# MegaSound9x_HaGeHa_SIP_v1.net
KiCad netlist of a schematic drawn in EAGLE
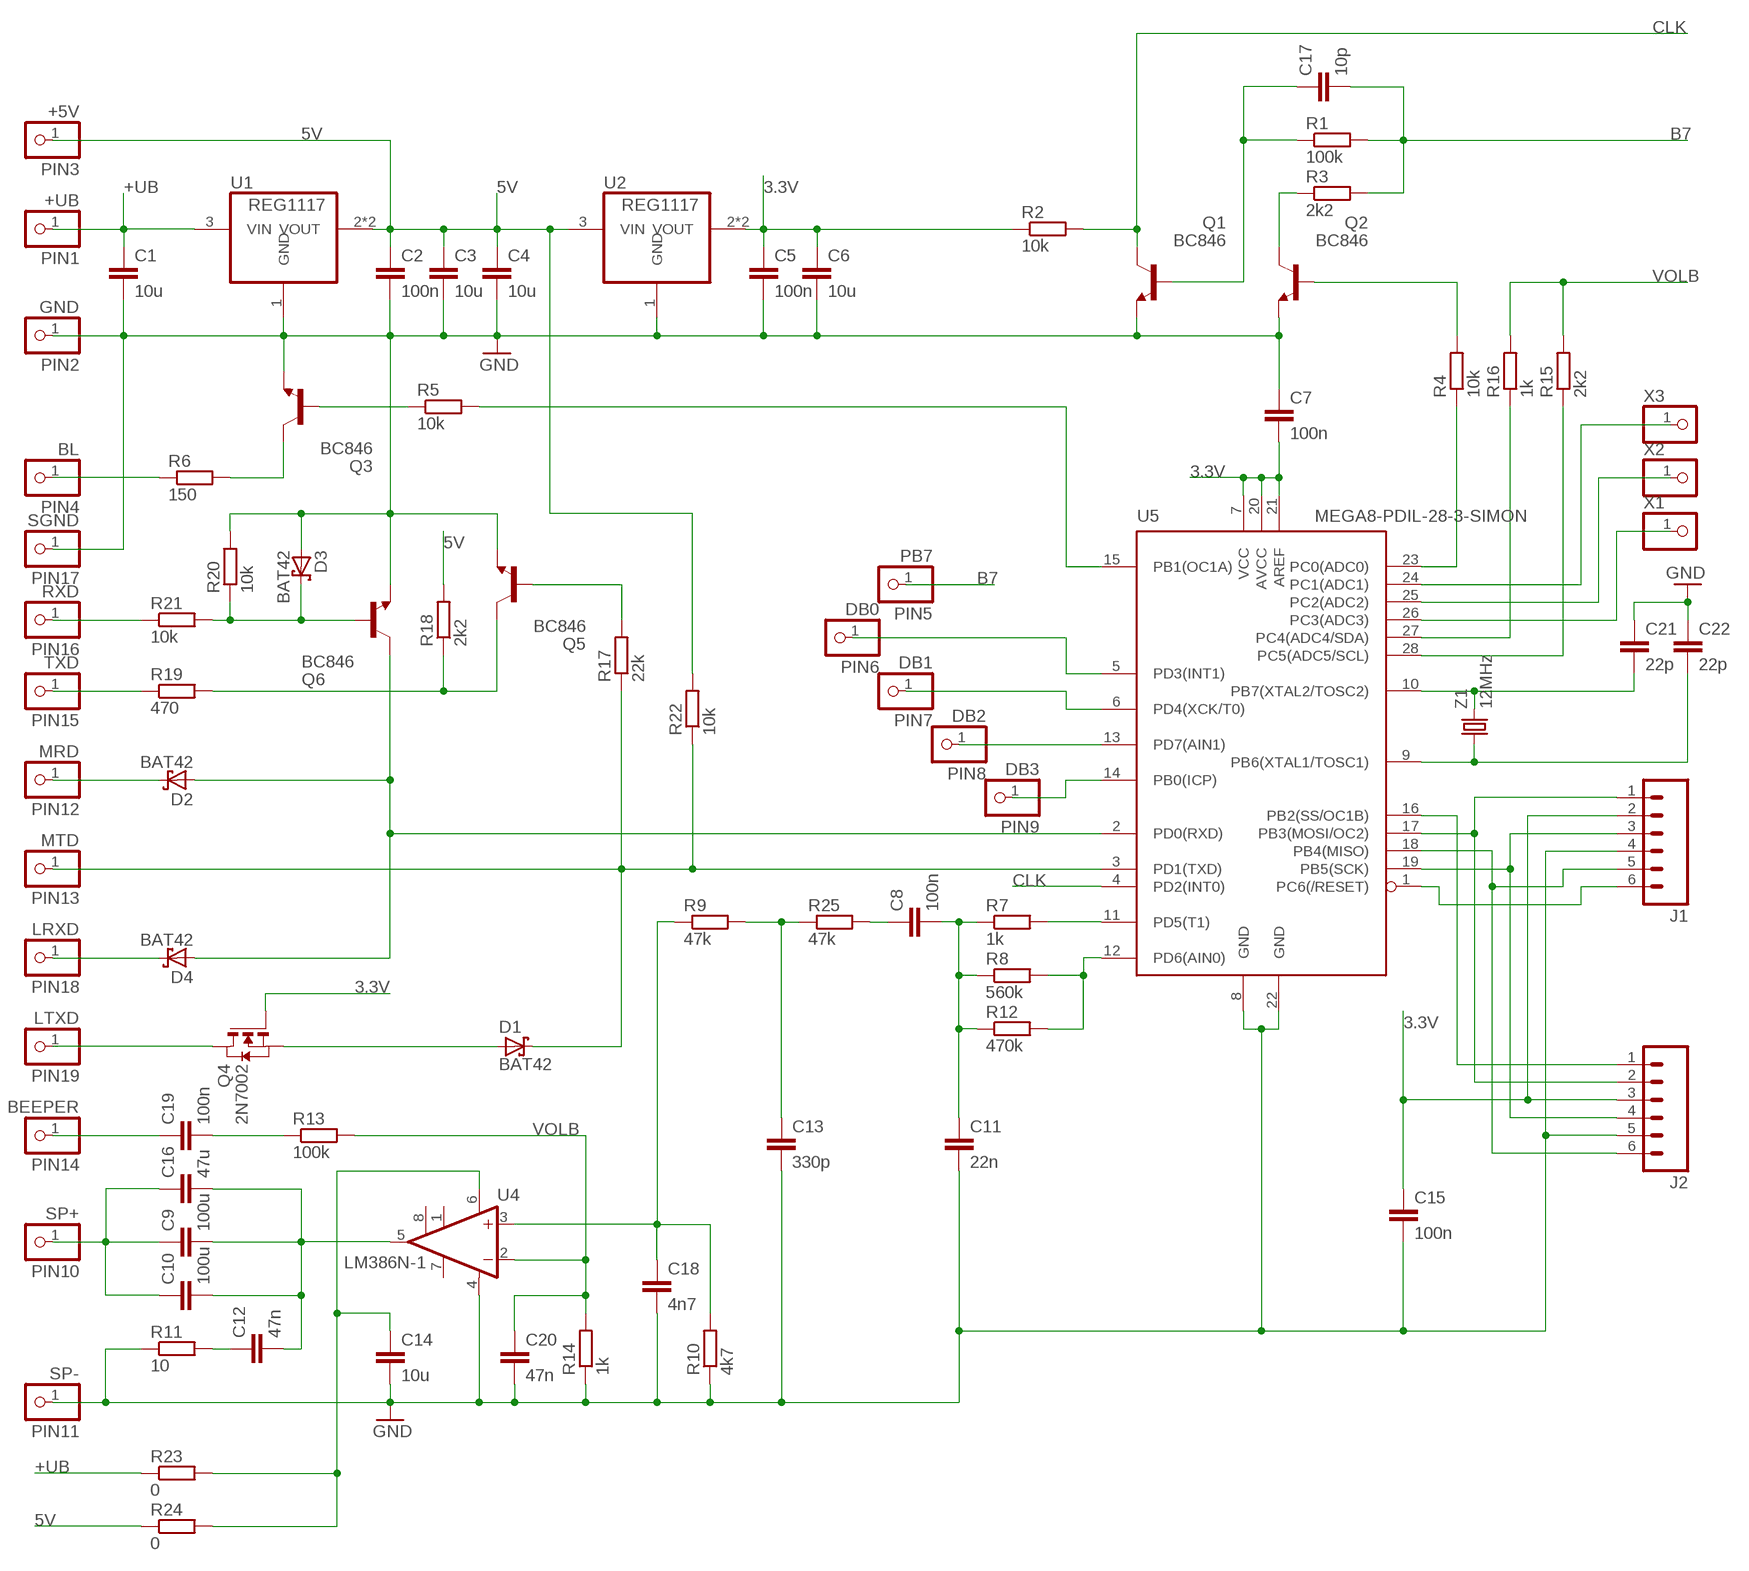
[diagram p0: schematic, sheet 1]

(export (version "E")
  (design (tool "Eeschema 10.0.6"))
  (components
    (comp (ref "+5V")
      (value "PIN3")
      (footprint "eagle-import:1X01")
      (libsource (lib "eagle-import") (part "PINHD-1X1"))
    )
    (comp (ref "+UB")
      (value "PIN1")
      (footprint "eagle-import:1X01")
      (libsource (lib "eagle-import") (part "PINHD-1X1"))
    )
    (comp (ref "BEEPER")
      (value "PIN14")
      (footprint "eagle-import:1X01")
      (libsource (lib "eagle-import") (part "PINHD-1X1"))
    )
    (comp (ref "BL")
      (value "PIN4")
      (footprint "eagle-import:1X01")
      (libsource (lib "eagle-import") (part "PINHD-1X1"))
    )
    (comp (ref "C1")
      (value "10u")
      (footprint "eagle-import:C1206")
      (libsource (lib "eagle-import") (part "C-EUC1206"))
    )
    (comp (ref "C2")
      (value "100n")
      (footprint "eagle-import:C1206")
      (libsource (lib "eagle-import") (part "C-EUC1206"))
    )
    (comp (ref "C3")
      (value "10u")
      (footprint "eagle-import:C1206")
      (libsource (lib "eagle-import") (part "C-EUC1206"))
    )
    (comp (ref "C4")
      (value "10u")
      (footprint "eagle-import:C1206")
      (libsource (lib "eagle-import") (part "C-EUC1206"))
    )
    (comp (ref "C5")
      (value "100n")
      (footprint "eagle-import:C1206")
      (libsource (lib "eagle-import") (part "C-EUC1206"))
    )
    (comp (ref "C6")
      (value "10u")
      (footprint "eagle-import:C1206")
      (libsource (lib "eagle-import") (part "C-EUC1206"))
    )
    (comp (ref "C7")
      (value "100n")
      (footprint "eagle-import:C1206")
      (libsource (lib "eagle-import") (part "C-EUC1206"))
    )
    (comp (ref "C8")
      (value "100n")
      (footprint "eagle-import:C1206")
      (libsource (lib "eagle-import") (part "C-EUC1206"))
    )
    (comp (ref "C9")
      (value "100u")
      (footprint "eagle-import:C1206")
      (libsource (lib "eagle-import") (part "C-EUC1206"))
    )
    (comp (ref "C10")
      (value "100u")
      (footprint "eagle-import:C1206")
      (libsource (lib "eagle-import") (part "C-EUC1206"))
    )
    (comp (ref "C11")
      (value "22n")
      (footprint "eagle-import:C1206")
      (libsource (lib "eagle-import") (part "C-EUC1206"))
    )
    (comp (ref "C12")
      (value "47n")
      (footprint "eagle-import:C1206")
      (libsource (lib "eagle-import") (part "C-EUC1206"))
    )
    (comp (ref "C13")
      (value "330p")
      (footprint "eagle-import:C1206")
      (libsource (lib "eagle-import") (part "C-EUC1206"))
    )
    (comp (ref "C14")
      (value "10u")
      (footprint "eagle-import:C1206")
      (libsource (lib "eagle-import") (part "C-EUC1206"))
    )
    (comp (ref "C15")
      (value "100n")
      (footprint "eagle-import:C1206")
      (libsource (lib "eagle-import") (part "C-EUC1206"))
    )
    (comp (ref "C16")
      (value "47u")
      (footprint "eagle-import:C1206")
      (libsource (lib "eagle-import") (part "C-EUC1206"))
    )
    (comp (ref "C17")
      (value "10p")
      (footprint "eagle-import:C1206")
      (libsource (lib "eagle-import") (part "C-EUC1206"))
    )
    (comp (ref "C18")
      (value "4n7")
      (footprint "eagle-import:C1206")
      (libsource (lib "eagle-import") (part "C-EUC1206"))
    )
    (comp (ref "C19")
      (value "100n")
      (footprint "eagle-import:C1206")
      (libsource (lib "eagle-import") (part "C-EUC1206"))
    )
    (comp (ref "C20")
      (value "47n")
      (footprint "eagle-import:C1206")
      (libsource (lib "eagle-import") (part "C-EUC1206"))
    )
    (comp (ref "C21")
      (value "22p")
      (footprint "eagle-import:C1206")
      (libsource (lib "eagle-import") (part "C-EUC1206"))
    )
    (comp (ref "C22")
      (value "22p")
      (footprint "eagle-import:C1206")
      (libsource (lib "eagle-import") (part "C-EUC1206"))
    )
    (comp (ref "D1")
      (value "BAT42")
      (footprint "eagle-import:SOD123")
      (libsource (lib "eagle-import") (part "BAT42"))
    )
    (comp (ref "D2")
      (value "BAT42")
      (footprint "eagle-import:SOD123")
      (libsource (lib "eagle-import") (part "BAT42"))
    )
    (comp (ref "D3")
      (value "BAT42")
      (footprint "eagle-import:SOD123")
      (libsource (lib "eagle-import") (part "BAT42"))
    )
    (comp (ref "D4")
      (value "BAT42")
      (footprint "eagle-import:SOD123")
      (libsource (lib "eagle-import") (part "BAT42"))
    )
    (comp (ref "DB0")
      (value "PIN6")
      (footprint "eagle-import:1X01")
      (libsource (lib "eagle-import") (part "PINHD-1X1"))
    )
    (comp (ref "DB1")
      (value "PIN7")
      (footprint "eagle-import:1X01")
      (libsource (lib "eagle-import") (part "PINHD-1X1"))
    )
    (comp (ref "DB2")
      (value "PIN8")
      (footprint "eagle-import:1X01")
      (libsource (lib "eagle-import") (part "PINHD-1X1"))
    )
    (comp (ref "DB3")
      (value "PIN9")
      (footprint "eagle-import:1X01")
      (libsource (lib "eagle-import") (part "PINHD-1X1"))
    )
    (comp (ref "GND")
      (value "PIN2")
      (footprint "eagle-import:1X01")
      (libsource (lib "eagle-import") (part "PINHD-1X1"))
    )
    (comp (ref "J1")
      (value "M06SIP")
      (footprint "eagle-import:1X06")
      (libsource (lib "eagle-import") (part "M06SIP"))
    )
    (comp (ref "J2")
      (value "M06SIP")
      (footprint "eagle-import:1X06")
      (libsource (lib "eagle-import") (part "M06SIP"))
    )
    (comp (ref "LRXD")
      (value "PIN18")
      (footprint "eagle-import:1X01")
      (libsource (lib "eagle-import") (part "PINHD-1X1"))
    )
    (comp (ref "LTXD")
      (value "PIN19")
      (footprint "eagle-import:1X01")
      (libsource (lib "eagle-import") (part "PINHD-1X1"))
    )
    (comp (ref "MRD")
      (value "PIN12")
      (footprint "eagle-import:1X01")
      (libsource (lib "eagle-import") (part "PINHD-1X1"))
    )
    (comp (ref "MTD")
      (value "PIN13")
      (footprint "eagle-import:1X01")
      (libsource (lib "eagle-import") (part "PINHD-1X1"))
    )
    (comp (ref "PB7")
      (value "PIN5")
      (footprint "eagle-import:1X01")
      (libsource (lib "eagle-import") (part "PINHD-1X1"))
    )
    (comp (ref "Q1")
      (value "BC846")
      (footprint "eagle-import:SOT23")
      (libsource (lib "eagle-import") (part "BC846"))
    )
    (comp (ref "Q2")
      (value "BC846")
      (footprint "eagle-import:SOT23")
      (libsource (lib "eagle-import") (part "BC846"))
    )
    (comp (ref "Q3")
      (value "BC846")
      (footprint "eagle-import:SOT23")
      (libsource (lib "eagle-import") (part "BC846"))
    )
    (comp (ref "Q4")
      (value "2N7002")
      (footprint "eagle-import:SOT-23")
      (libsource (lib "eagle-import") (part "NMOSSOT23"))
    )
    (comp (ref "Q5")
      (value "BC846")
      (footprint "eagle-import:SOT23")
      (libsource (lib "eagle-import") (part "BC846"))
    )
    (comp (ref "Q6")
      (value "BC846")
      (footprint "eagle-import:SOT23")
      (libsource (lib "eagle-import") (part "BC846"))
    )
    (comp (ref "R1")
      (value "100k")
      (footprint "eagle-import:R1206")
      (libsource (lib "eagle-import") (part "R-EU_R1206"))
    )
    (comp (ref "R2")
      (value "10k")
      (footprint "eagle-import:R1206")
      (libsource (lib "eagle-import") (part "R-EU_R1206"))
    )
    (comp (ref "R3")
      (value "2k2")
      (footprint "eagle-import:R1206")
      (libsource (lib "eagle-import") (part "R-EU_R1206"))
    )
    (comp (ref "R4")
      (value "10k")
      (footprint "eagle-import:R1206")
      (libsource (lib "eagle-import") (part "R-EU_R1206"))
    )
    (comp (ref "R5")
      (value "10k")
      (footprint "eagle-import:R1206")
      (libsource (lib "eagle-import") (part "R-EU_R1206"))
    )
    (comp (ref "R6")
      (value "150")
      (footprint "eagle-import:R1206")
      (libsource (lib "eagle-import") (part "R-EU_R1206"))
    )
    (comp (ref "R7")
      (value "1k")
      (footprint "eagle-import:R1206")
      (libsource (lib "eagle-import") (part "R-EU_R1206"))
    )
    (comp (ref "R8")
      (value "560k")
      (footprint "eagle-import:R1206")
      (libsource (lib "eagle-import") (part "R-EU_R1206"))
    )
    (comp (ref "R9")
      (value "47k")
      (footprint "eagle-import:R1206")
      (libsource (lib "eagle-import") (part "R-EU_R1206"))
    )
    (comp (ref "R10")
      (value "4k7")
      (footprint "eagle-import:R1206")
      (libsource (lib "eagle-import") (part "R-EU_R1206"))
    )
    (comp (ref "R11")
      (value "10")
      (footprint "eagle-import:R1206")
      (libsource (lib "eagle-import") (part "R-EU_R1206"))
    )
    (comp (ref "R12")
      (value "470k")
      (footprint "eagle-import:R1206")
      (libsource (lib "eagle-import") (part "R-EU_R1206"))
    )
    (comp (ref "R13")
      (value "100k")
      (footprint "eagle-import:R1206")
      (libsource (lib "eagle-import") (part "R-EU_R1206"))
    )
    (comp (ref "R14")
      (value "1k")
      (footprint "eagle-import:R1206")
      (libsource (lib "eagle-import") (part "R-EU_R1206"))
    )
    (comp (ref "R15")
      (value "2k2")
      (footprint "eagle-import:R1206")
      (libsource (lib "eagle-import") (part "R-EU_R1206"))
    )
    (comp (ref "R16")
      (value "1k")
      (footprint "eagle-import:R1206")
      (libsource (lib "eagle-import") (part "R-EU_R1206"))
    )
    (comp (ref "R17")
      (value "22k")
      (footprint "eagle-import:R1206")
      (libsource (lib "eagle-import") (part "R-EU_R1206"))
    )
    (comp (ref "R18")
      (value "2k2")
      (footprint "eagle-import:R1206")
      (libsource (lib "eagle-import") (part "R-EU_R1206"))
    )
    (comp (ref "R19")
      (value "470")
      (footprint "eagle-import:R1206")
      (libsource (lib "eagle-import") (part "R-EU_R1206"))
    )
    (comp (ref "R20")
      (value "10k")
      (footprint "eagle-import:R1206")
      (libsource (lib "eagle-import") (part "R-EU_R1206"))
    )
    (comp (ref "R21")
      (value "10k")
      (footprint "eagle-import:R1206")
      (libsource (lib "eagle-import") (part "R-EU_R1206"))
    )
    (comp (ref "R22")
      (value "10k")
      (footprint "eagle-import:R1206")
      (libsource (lib "eagle-import") (part "R-EU_R1206"))
    )
    (comp (ref "R23")
      (value "0")
      (footprint "eagle-import:R1206")
      (libsource (lib "eagle-import") (part "R-EU_R1206"))
    )
    (comp (ref "R24")
      (value "0")
      (footprint "eagle-import:R1206")
      (libsource (lib "eagle-import") (part "R-EU_R1206"))
    )
    (comp (ref "R25")
      (value "47k")
      (footprint "eagle-import:R1206")
      (libsource (lib "eagle-import") (part "R-EU_R1206"))
    )
    (comp (ref "RXD")
      (value "PIN16")
      (footprint "eagle-import:1X01")
      (libsource (lib "eagle-import") (part "PINHD-1X1"))
    )
    (comp (ref "SGND")
      (value "PIN17")
      (footprint "eagle-import:1X01")
      (libsource (lib "eagle-import") (part "PINHD-1X1"))
    )
    (comp (ref "SP+")
      (value "PIN10")
      (footprint "eagle-import:1X01")
      (libsource (lib "eagle-import") (part "PINHD-1X1"))
    )
    (comp (ref "SP-")
      (value "PIN11")
      (footprint "eagle-import:1X01")
      (libsource (lib "eagle-import") (part "PINHD-1X1"))
    )
    (comp (ref "TXD")
      (value "PIN15")
      (footprint "eagle-import:1X01")
      (libsource (lib "eagle-import") (part "PINHD-1X1"))
    )
    (comp (ref "U1")
      (value "REG1117")
      (footprint "eagle-import:SOT223")
      (libsource (lib "eagle-import") (part "REG1117"))
    )
    (comp (ref "U2")
      (value "REG1117")
      (footprint "eagle-import:SOT223")
      (fields
        (field (name "MPN") "REG1117")
        (field (name "OC_FARNELL") "1097566")
        (field (name "OC_NEWARK") "14P6981")
      )
      (libsource (lib "eagle-import") (part "REG1117"))
    )
    (comp (ref "U4")
      (value "LM386N-1")
      (footprint "eagle-import:DIL08")
      (libsource (lib "eagle-import") (part "LM386?-N1"))
    )
    (comp (ref "U5")
      (value "MEGA8-PDIL-28-3-SIMON")
      (footprint "eagle-import:DIL28-3-SIMON")
      (libsource (lib "eagle-import") (part "MEGA8-PDIL-28-3-SIMON"))
    )
    (comp (ref "X1")
      (value "PINHD-1X1")
      (footprint "eagle-import:1X01")
      (libsource (lib "eagle-import") (part "PINHD-1X1"))
    )
    (comp (ref "X2")
      (value "PINHD-1X1")
      (footprint "eagle-import:1X01")
      (libsource (lib "eagle-import") (part "PINHD-1X1"))
    )
    (comp (ref "X3")
      (value "PINHD-1X1")
      (footprint "eagle-import:1X01")
      (libsource (lib "eagle-import") (part "PINHD-1X1"))
    )
    (comp (ref "Z1")
      (value "12MHz")
      (footprint "eagle-import:HC49US")
      (libsource (lib "eagle-import") (part "CRYSTALHC49US"))
    )
  )
  (nets
    (net (code "1") (name "/+UB") (class "Default")
      (node (ref "+UB") (pin "1") (pinfunction "1_1") (pintype "passive"))
      (node (ref "C1") (pin "1") (pinfunction "1_1") (pintype "passive"))
      (node (ref "R23") (pin "1") (pinfunction "1_1") (pintype "passive"))
      (node (ref "U1") (pin "3") (pinfunction "VIN_3") (pintype "input"))
    )
    (net (code "2") (name "/3.3V") (class "Default")
      (node (ref "C15") (pin "1") (pinfunction "1_1") (pintype "passive"))
      (node (ref "C5") (pin "1") (pinfunction "1_1") (pintype "passive"))
      (node (ref "C6") (pin "1") (pinfunction "1_1") (pintype "passive"))
      (node (ref "C7") (pin "2") (pinfunction "2_2") (pintype "passive"))
      (node (ref "J1") (pin "2") (pinfunction "2_2") (pintype "passive"))
      (node (ref "J2") (pin "3") (pinfunction "3_3") (pintype "passive"))
      (node (ref "Q4") (pin "3") (pinfunction "G_3") (pintype "passive"))
      (node (ref "R2") (pin "1") (pinfunction "1_1") (pintype "passive"))
      (node (ref "U2") (pin "2") (pinfunction "VOUT_2") (pintype "output"))
      (node (ref "U2") (pin "4") (pinfunction "VOUT_4") (pintype "output"))
      (node (ref "U5") (pin "20") (pinfunction "AVCC_20") (pintype "power_in"))
      (node (ref "U5") (pin "21") (pinfunction "AREF_21") (pintype "passive"))
      (node (ref "U5") (pin "7") (pinfunction "VCC_7") (pintype "power_in"))
    )
    (net (code "3") (name "/5V") (class "Default")
      (node (ref "+5V") (pin "1") (pinfunction "1_1") (pintype "passive"))
      (node (ref "C2") (pin "1") (pinfunction "1_1") (pintype "passive"))
      (node (ref "C3") (pin "1") (pinfunction "1_1") (pintype "passive"))
      (node (ref "C4") (pin "1") (pinfunction "1_1") (pintype "passive"))
      (node (ref "R18") (pin "2") (pinfunction "2_2") (pintype "passive"))
      (node (ref "R22") (pin "2") (pinfunction "2_2") (pintype "passive"))
      (node (ref "R24") (pin "1") (pinfunction "1_1") (pintype "passive"))
      (node (ref "U1") (pin "2") (pinfunction "VOUT_2") (pintype "output"))
      (node (ref "U1") (pin "4") (pinfunction "VOUT_4") (pintype "output"))
      (node (ref "U2") (pin "3") (pinfunction "VIN_3") (pintype "input"))
    )
    (net (code "4") (name "/B7") (class "Default")
      (node (ref "C17") (pin "2") (pinfunction "2_2") (pintype "passive"))
      (node (ref "PB7") (pin "1") (pinfunction "1_1") (pintype "passive"))
      (node (ref "R1") (pin "2") (pinfunction "2_2") (pintype "passive"))
      (node (ref "R3") (pin "2") (pinfunction "2_2") (pintype "passive"))
    )
    (net (code "5") (name "/CLK") (class "Default")
      (node (ref "Q1") (pin "3") (pinfunction "C_3") (pintype "passive"))
      (node (ref "R2") (pin "2") (pinfunction "2_2") (pintype "passive"))
      (node (ref "U5") (pin "4") (pinfunction "PD2(INT0)_4") (pintype "bidirectional"))
    )
    (net (code "6") (name "/VOLB") (class "Default")
      (node (ref "C20") (pin "1") (pinfunction "1_1") (pintype "passive"))
      (node (ref "R13") (pin "2") (pinfunction "2_2") (pintype "passive"))
      (node (ref "R14") (pin "2") (pinfunction "2_2") (pintype "passive"))
      (node (ref "R15") (pin "2") (pinfunction "2_2") (pintype "passive"))
      (node (ref "R16") (pin "2") (pinfunction "2_2") (pintype "passive"))
      (node (ref "U4") (pin "2") (pinfunction "-IN_2") (pintype "input"))
    )
    (net (code "7") (name "GND") (class "Default")
      (node (ref "C1") (pin "2") (pinfunction "2_2") (pintype "passive"))
      (node (ref "C11") (pin "2") (pinfunction "2_2") (pintype "passive"))
      (node (ref "C13") (pin "2") (pinfunction "2_2") (pintype "passive"))
      (node (ref "C14") (pin "2") (pinfunction "2_2") (pintype "passive"))
      (node (ref "C15") (pin "2") (pinfunction "2_2") (pintype "passive"))
      (node (ref "C18") (pin "2") (pinfunction "2_2") (pintype "passive"))
      (node (ref "C2") (pin "2") (pinfunction "2_2") (pintype "passive"))
      (node (ref "C20") (pin "2") (pinfunction "2_2") (pintype "passive"))
      (node (ref "C21") (pin "1") (pinfunction "1_1") (pintype "passive"))
      (node (ref "C22") (pin "1") (pinfunction "1_1") (pintype "passive"))
      (node (ref "C3") (pin "2") (pinfunction "2_2") (pintype "passive"))
      (node (ref "C4") (pin "2") (pinfunction "2_2") (pintype "passive"))
      (node (ref "C5") (pin "2") (pinfunction "2_2") (pintype "passive"))
      (node (ref "C6") (pin "2") (pinfunction "2_2") (pintype "passive"))
      (node (ref "C7") (pin "1") (pinfunction "1_1") (pintype "passive"))
      (node (ref "D3") (pin "A") (pinfunction "A_A") (pintype "passive"))
      (node (ref "GND") (pin "1") (pinfunction "1_1") (pintype "passive"))
      (node (ref "J1") (pin "4") (pinfunction "4_4") (pintype "passive"))
      (node (ref "J2") (pin "5") (pinfunction "5_5") (pintype "passive"))
      (node (ref "Q1") (pin "2") (pinfunction "E_2") (pintype "passive"))
      (node (ref "Q2") (pin "2") (pinfunction "E_2") (pintype "passive"))
      (node (ref "Q3") (pin "2") (pinfunction "E_2") (pintype "passive"))
      (node (ref "Q5") (pin "2") (pinfunction "E_2") (pintype "passive"))
      (node (ref "Q6") (pin "2") (pinfunction "E_2") (pintype "passive"))
      (node (ref "R10") (pin "1") (pinfunction "1_1") (pintype "passive"))
      (node (ref "R11") (pin "1") (pinfunction "1_1") (pintype "passive"))
      (node (ref "R14") (pin "1") (pinfunction "1_1") (pintype "passive"))
      (node (ref "R20") (pin "2") (pinfunction "2_2") (pintype "passive"))
      (node (ref "SGND") (pin "1") (pinfunction "1_1") (pintype "passive"))
      (node (ref "SP-") (pin "1") (pinfunction "1_1") (pintype "passive"))
      (node (ref "U1") (pin "1") (pinfunction "GND_1") (pintype "power_in"))
      (node (ref "U2") (pin "1") (pinfunction "GND_1") (pintype "power_in"))
      (node (ref "U4") (pin "4") (pinfunction "GND_4") (pintype "power_in"))
      (node (ref "U5") (pin "22") (pinfunction "GND_22") (pintype "power_in"))
      (node (ref "U5") (pin "8") (pinfunction "GND_8") (pintype "power_in"))
    )
    (net (code "8") (name "Net-(BEEPER-Pad1)") (class "Default")
      (node (ref "BEEPER") (pin "1") (pinfunction "1_1") (pintype "passive"))
      (node (ref "C19") (pin "1") (pinfunction "1_1") (pintype "passive"))
    )
    (net (code "9") (name "Net-(BL-Pad1)") (class "Default")
      (node (ref "BL") (pin "1") (pinfunction "1_1") (pintype "passive"))
      (node (ref "R6") (pin "1") (pinfunction "1_1") (pintype "passive"))
    )
    (net (code "10") (name "Net-(C8-Pad1)") (class "Default")
      (node (ref "C8") (pin "1") (pinfunction "1_1") (pintype "passive"))
      (node (ref "R25") (pin "2") (pinfunction "2_2") (pintype "passive"))
    )
    (net (code "11") (name "Net-(C10-Pad1)") (class "Default")
      (node (ref "C10") (pin "1") (pinfunction "1_1") (pintype "passive"))
      (node (ref "C16") (pin "1") (pinfunction "1_1") (pintype "passive"))
      (node (ref "C9") (pin "1") (pinfunction "1_1") (pintype "passive"))
      (node (ref "SP+") (pin "1") (pinfunction "1_1") (pintype "passive"))
    )
    (net (code "12") (name "Net-(C11-Pad1)") (class "Default")
      (node (ref "C11") (pin "1") (pinfunction "1_1") (pintype "passive"))
      (node (ref "C8") (pin "2") (pinfunction "2_2") (pintype "passive"))
      (node (ref "R12") (pin "1") (pinfunction "1_1") (pintype "passive"))
      (node (ref "R7") (pin "1") (pinfunction "1_1") (pintype "passive"))
      (node (ref "R8") (pin "1") (pinfunction "1_1") (pintype "passive"))
    )
    (net (code "13") (name "Net-(C12-Pad1)") (class "Default")
      (node (ref "C12") (pin "1") (pinfunction "1_1") (pintype "passive"))
      (node (ref "R11") (pin "2") (pinfunction "2_2") (pintype "passive"))
    )
    (net (code "14") (name "Net-(C13-Pad1)") (class "Default")
      (node (ref "C13") (pin "1") (pinfunction "1_1") (pintype "passive"))
      (node (ref "R25") (pin "1") (pinfunction "1_1") (pintype "passive"))
      (node (ref "R9") (pin "2") (pinfunction "2_2") (pintype "passive"))
    )
    (net (code "15") (name "Net-(C19-Pad2)") (class "Default")
      (node (ref "C19") (pin "2") (pinfunction "2_2") (pintype "passive"))
      (node (ref "R13") (pin "1") (pinfunction "1_1") (pintype "passive"))
    )
    (net (code "16") (name "Net-(D2-PadC)") (class "Default")
      (node (ref "D2") (pin "C") (pinfunction "C_C") (pintype "passive"))
      (node (ref "MRD") (pin "1") (pinfunction "1_1") (pintype "passive"))
    )
    (net (code "17") (name "Net-(D4-PadC)") (class "Default")
      (node (ref "D4") (pin "C") (pinfunction "C_C") (pintype "passive"))
      (node (ref "LRXD") (pin "1") (pinfunction "1_1") (pintype "passive"))
    )
    (net (code "18") (name "Net-(Q1-B)") (class "Default")
      (node (ref "C17") (pin "1") (pinfunction "1_1") (pintype "passive"))
      (node (ref "Q1") (pin "1") (pinfunction "B_1") (pintype "passive"))
      (node (ref "R1") (pin "1") (pinfunction "1_1") (pintype "passive"))
    )
    (net (code "19") (name "Net-(Q2-B)") (class "Default")
      (node (ref "Q2") (pin "1") (pinfunction "B_1") (pintype "passive"))
      (node (ref "R4") (pin "2") (pinfunction "2_2") (pintype "passive"))
    )
    (net (code "20") (name "Net-(Q2-C)") (class "Default")
      (node (ref "Q2") (pin "3") (pinfunction "C_3") (pintype "passive"))
      (node (ref "R3") (pin "1") (pinfunction "1_1") (pintype "passive"))
    )
    (net (code "21") (name "Net-(Q3-B)") (class "Default")
      (node (ref "Q3") (pin "1") (pinfunction "B_1") (pintype "passive"))
      (node (ref "R5") (pin "1") (pinfunction "1_1") (pintype "passive"))
    )
    (net (code "22") (name "Net-(Q3-C)") (class "Default")
      (node (ref "Q3") (pin "3") (pinfunction "C_3") (pintype "passive"))
      (node (ref "R6") (pin "2") (pinfunction "2_2") (pintype "passive"))
    )
    (net (code "23") (name "Net-(Q4-D)") (class "Default")
      (node (ref "LTXD") (pin "1") (pinfunction "1_1") (pintype "passive"))
      (node (ref "Q4") (pin "1") (pinfunction "D_1") (pintype "passive"))
    )
    (net (code "24") (name "Net-(Q4-S)") (class "Default")
      (node (ref "D1") (pin "A") (pinfunction "A_A") (pintype "passive"))
      (node (ref "Q4") (pin "2") (pinfunction "S_2") (pintype "passive"))
    )
    (net (code "25") (name "Net-(Q5-B)") (class "Default")
      (node (ref "Q5") (pin "1") (pinfunction "B_1") (pintype "passive"))
      (node (ref "R17") (pin "2") (pinfunction "2_2") (pintype "passive"))
    )
    (net (code "26") (name "Net-(Q5-C)") (class "Default")
      (node (ref "Q5") (pin "3") (pinfunction "C_3") (pintype "passive"))
      (node (ref "R18") (pin "1") (pinfunction "1_1") (pintype "passive"))
      (node (ref "R19") (pin "2") (pinfunction "2_2") (pintype "passive"))
    )
    (net (code "27") (name "Net-(Q6-B)") (class "Default")
      (node (ref "D3") (pin "C") (pinfunction "C_C") (pintype "passive"))
      (node (ref "Q6") (pin "1") (pinfunction "B_1") (pintype "passive"))
      (node (ref "R20") (pin "1") (pinfunction "1_1") (pintype "passive"))
      (node (ref "R21") (pin "2") (pinfunction "2_2") (pintype "passive"))
    )
    (net (code "28") (name "Net-(Q6-C)") (class "Default")
      (node (ref "D2") (pin "A") (pinfunction "A_A") (pintype "passive"))
      (node (ref "D4") (pin "A") (pinfunction "A_A") (pintype "passive"))
      (node (ref "Q6") (pin "3") (pinfunction "C_3") (pintype "passive"))
      (node (ref "U5") (pin "2") (pinfunction "PD0(RXD)_2") (pintype "bidirectional"))
    )
    (net (code "29") (name "Net-(R19-Pad1)") (class "Default")
      (node (ref "R19") (pin "1") (pinfunction "1_1") (pintype "passive"))
      (node (ref "TXD") (pin "1") (pinfunction "1_1") (pintype "passive"))
    )
    (net (code "30") (name "Net-(R21-Pad1)") (class "Default")
      (node (ref "R21") (pin "1") (pinfunction "1_1") (pintype "passive"))
      (node (ref "RXD") (pin "1") (pinfunction "1_1") (pintype "passive"))
    )
    (net (code "31") (name "Net-(U4-+IN)") (class "Default")
      (node (ref "C18") (pin "1") (pinfunction "1_1") (pintype "passive"))
      (node (ref "R10") (pin "2") (pinfunction "2_2") (pintype "passive"))
      (node (ref "R9") (pin "1") (pinfunction "1_1") (pintype "passive"))
      (node (ref "U4") (pin "3") (pinfunction "+IN_3") (pintype "input"))
    )
    (net (code "32") (name "Net-(U4-OUT)") (class "Default")
      (node (ref "C10") (pin "2") (pinfunction "2_2") (pintype "passive"))
      (node (ref "C12") (pin "2") (pinfunction "2_2") (pintype "passive"))
      (node (ref "C16") (pin "2") (pinfunction "2_2") (pintype "passive"))
      (node (ref "C9") (pin "2") (pinfunction "2_2") (pintype "passive"))
      (node (ref "U4") (pin "5") (pinfunction "OUT_5") (pintype "output"))
    )
    (net (code "33") (name "Net-(U4-VS)") (class "Default")
      (node (ref "C14") (pin "1") (pinfunction "1_1") (pintype "passive"))
      (node (ref "R23") (pin "2") (pinfunction "2_2") (pintype "passive"))
      (node (ref "R24") (pin "2") (pinfunction "2_2") (pintype "passive"))
      (node (ref "U4") (pin "6") (pinfunction "VS_6") (pintype "power_in"))
    )
    (net (code "34") (name "Net-(U5-PB0(ICP))") (class "Default")
      (node (ref "DB3") (pin "1") (pinfunction "1_1") (pintype "passive"))
      (node (ref "U5") (pin "14") (pinfunction "PB0(ICP)_14") (pintype "bidirectional"))
    )
    (net (code "35") (name "Net-(U5-PB1(OC1A))") (class "Default")
      (node (ref "R5") (pin "2") (pinfunction "2_2") (pintype "passive"))
      (node (ref "U5") (pin "15") (pinfunction "PB1(OC1A)_15") (pintype "bidirectional"))
    )
    (net (code "36") (name "Net-(U5-PB2(SS{slash}OC1B))") (class "Default")
      (node (ref "J2") (pin "1") (pinfunction "1_1") (pintype "passive"))
      (node (ref "U5") (pin "16") (pinfunction "PB2(SS/OC1B)_16") (pintype "bidirectional"))
    )
    (net (code "37") (name "Net-(U5-PB3(MOSI{slash}OC2))") (class "Default")
      (node (ref "J1") (pin "1") (pinfunction "1_1") (pintype "passive"))
      (node (ref "J2") (pin "2") (pinfunction "2_2") (pintype "passive"))
      (node (ref "U5") (pin "17") (pinfunction "PB3(MOSI/OC2)_17") (pintype "bidirectional"))
    )
    (net (code "38") (name "Net-(U5-PB4(MISO))") (class "Default")
      (node (ref "J1") (pin "5") (pinfunction "5_5") (pintype "passive"))
      (node (ref "J2") (pin "6") (pinfunction "6_6") (pintype "passive"))
      (node (ref "U5") (pin "18") (pinfunction "PB4(MISO)_18") (pintype "bidirectional"))
    )
    (net (code "39") (name "Net-(U5-PB5(SCK))") (class "Default")
      (node (ref "J1") (pin "3") (pinfunction "3_3") (pintype "passive"))
      (node (ref "J2") (pin "4") (pinfunction "4_4") (pintype "passive"))
      (node (ref "U5") (pin "19") (pinfunction "PB5(SCK)_19") (pintype "bidirectional"))
    )
    (net (code "40") (name "Net-(U5-PB6(XTAL1{slash}TOSC1))") (class "Default")
      (node (ref "C22") (pin "2") (pinfunction "2_2") (pintype "passive"))
      (node (ref "U5") (pin "9") (pinfunction "PB6(XTAL1/TOSC1)_9") (pintype "bidirectional"))
      (node (ref "Z1") (pin "1") (pinfunction "1_1") (pintype "passive"))
    )
    (net (code "41") (name "Net-(U5-PB7(XTAL2{slash}TOSC2))") (class "Default")
      (node (ref "C21") (pin "2") (pinfunction "2_2") (pintype "passive"))
      (node (ref "U5") (pin "10") (pinfunction "PB7(XTAL2/TOSC2)_10") (pintype "bidirectional"))
      (node (ref "Z1") (pin "2") (pinfunction "2_2") (pintype "passive"))
    )
    (net (code "42") (name "Net-(U5-PC0(ADC0))") (class "Default")
      (node (ref "R4") (pin "1") (pinfunction "1_1") (pintype "passive"))
      (node (ref "U5") (pin "23") (pinfunction "PC0(ADC0)_23") (pintype "bidirectional"))
    )
    (net (code "43") (name "Net-(U5-PC1(ADC1))") (class "Default")
      (node (ref "U5") (pin "24") (pinfunction "PC1(ADC1)_24") (pintype "bidirectional"))
      (node (ref "X3") (pin "1") (pinfunction "1_1") (pintype "passive"))
    )
    (net (code "44") (name "Net-(U5-PC2(ADC2))") (class "Default")
      (node (ref "U5") (pin "25") (pinfunction "PC2(ADC2)_25") (pintype "bidirectional"))
      (node (ref "X2") (pin "1") (pinfunction "1_1") (pintype "passive"))
    )
    (net (code "45") (name "Net-(U5-PC3(ADC3))") (class "Default")
      (node (ref "U5") (pin "26") (pinfunction "PC3(ADC3)_26") (pintype "bidirectional"))
      (node (ref "X1") (pin "1") (pinfunction "1_1") (pintype "passive"))
    )
    (net (code "46") (name "Net-(U5-PC4(ADC4{slash}SDA))") (class "Default")
      (node (ref "R16") (pin "1") (pinfunction "1_1") (pintype "passive"))
      (node (ref "U5") (pin "27") (pinfunction "PC4(ADC4/SDA)_27") (pintype "bidirectional"))
    )
    (net (code "47") (name "Net-(U5-PC5(ADC5{slash}SCL))") (class "Default")
      (node (ref "R15") (pin "1") (pinfunction "1_1") (pintype "passive"))
      (node (ref "U5") (pin "28") (pinfunction "PC5(ADC5/SCL)_28") (pintype "bidirectional"))
    )
    (net (code "48") (name "Net-(U5-PC6({slash}RESET))") (class "Default")
      (node (ref "J1") (pin "6") (pinfunction "6_6") (pintype "passive"))
      (node (ref "U5") (pin "1") (pinfunction "PC6(/RESET)_1") (pintype "bidirectional"))
    )
    (net (code "49") (name "Net-(U5-PD1(TXD))") (class "Default")
      (node (ref "D1") (pin "C") (pinfunction "C_C") (pintype "passive"))
      (node (ref "MTD") (pin "1") (pinfunction "1_1") (pintype "passive"))
      (node (ref "R17") (pin "1") (pinfunction "1_1") (pintype "passive"))
      (node (ref "R22") (pin "1") (pinfunction "1_1") (pintype "passive"))
      (node (ref "U5") (pin "3") (pinfunction "PD1(TXD)_3") (pintype "bidirectional"))
    )
    (net (code "50") (name "Net-(U5-PD3(INT1))") (class "Default")
      (node (ref "DB0") (pin "1") (pinfunction "1_1") (pintype "passive"))
      (node (ref "U5") (pin "5") (pinfunction "PD3(INT1)_5") (pintype "bidirectional"))
    )
    (net (code "51") (name "Net-(U5-PD4(XCK{slash}T0))") (class "Default")
      (node (ref "DB1") (pin "1") (pinfunction "1_1") (pintype "passive"))
      (node (ref "U5") (pin "6") (pinfunction "PD4(XCK/T0)_6") (pintype "bidirectional"))
    )
    (net (code "52") (name "Net-(U5-PD5(T1))") (class "Default")
      (node (ref "R7") (pin "2") (pinfunction "2_2") (pintype "passive"))
      (node (ref "U5") (pin "11") (pinfunction "PD5(T1)_11") (pintype "bidirectional"))
    )
    (net (code "53") (name "Net-(U5-PD6(AIN0))") (class "Default")
      (node (ref "R12") (pin "2") (pinfunction "2_2") (pintype "passive"))
      (node (ref "R8") (pin "2") (pinfunction "2_2") (pintype "passive"))
      (node (ref "U5") (pin "12") (pinfunction "PD6(AIN0)_12") (pintype "bidirectional"))
    )
    (net (code "54") (name "Net-(U5-PD7(AIN1))") (class "Default")
      (node (ref "DB2") (pin "1") (pinfunction "1_1") (pintype "passive"))
      (node (ref "U5") (pin "13") (pinfunction "PD7(AIN1)_13") (pintype "bidirectional"))
    )
    (net (code "55") (name "unconnected-(U4-BYPASS-Pad7)") (class "Default")
      (node (ref "U4") (pin "7") (pinfunction "BYPASS_7") (pintype "passive"))
    )
    (net (code "56") (name "unconnected-(U4-GAIN-Pad1)") (class "Default")
      (node (ref "U4") (pin "1") (pinfunction "GAIN_1") (pintype "passive"))
    )
    (net (code "57") (name "unconnected-(U4-GAIN-Pad8)") (class "Default")
      (node (ref "U4") (pin "8") (pinfunction "GAIN_8") (pintype "passive"))
    )
  )
)
